# HV_Sense.net
KiCad netlist of a schematic drawn in Altium Designer
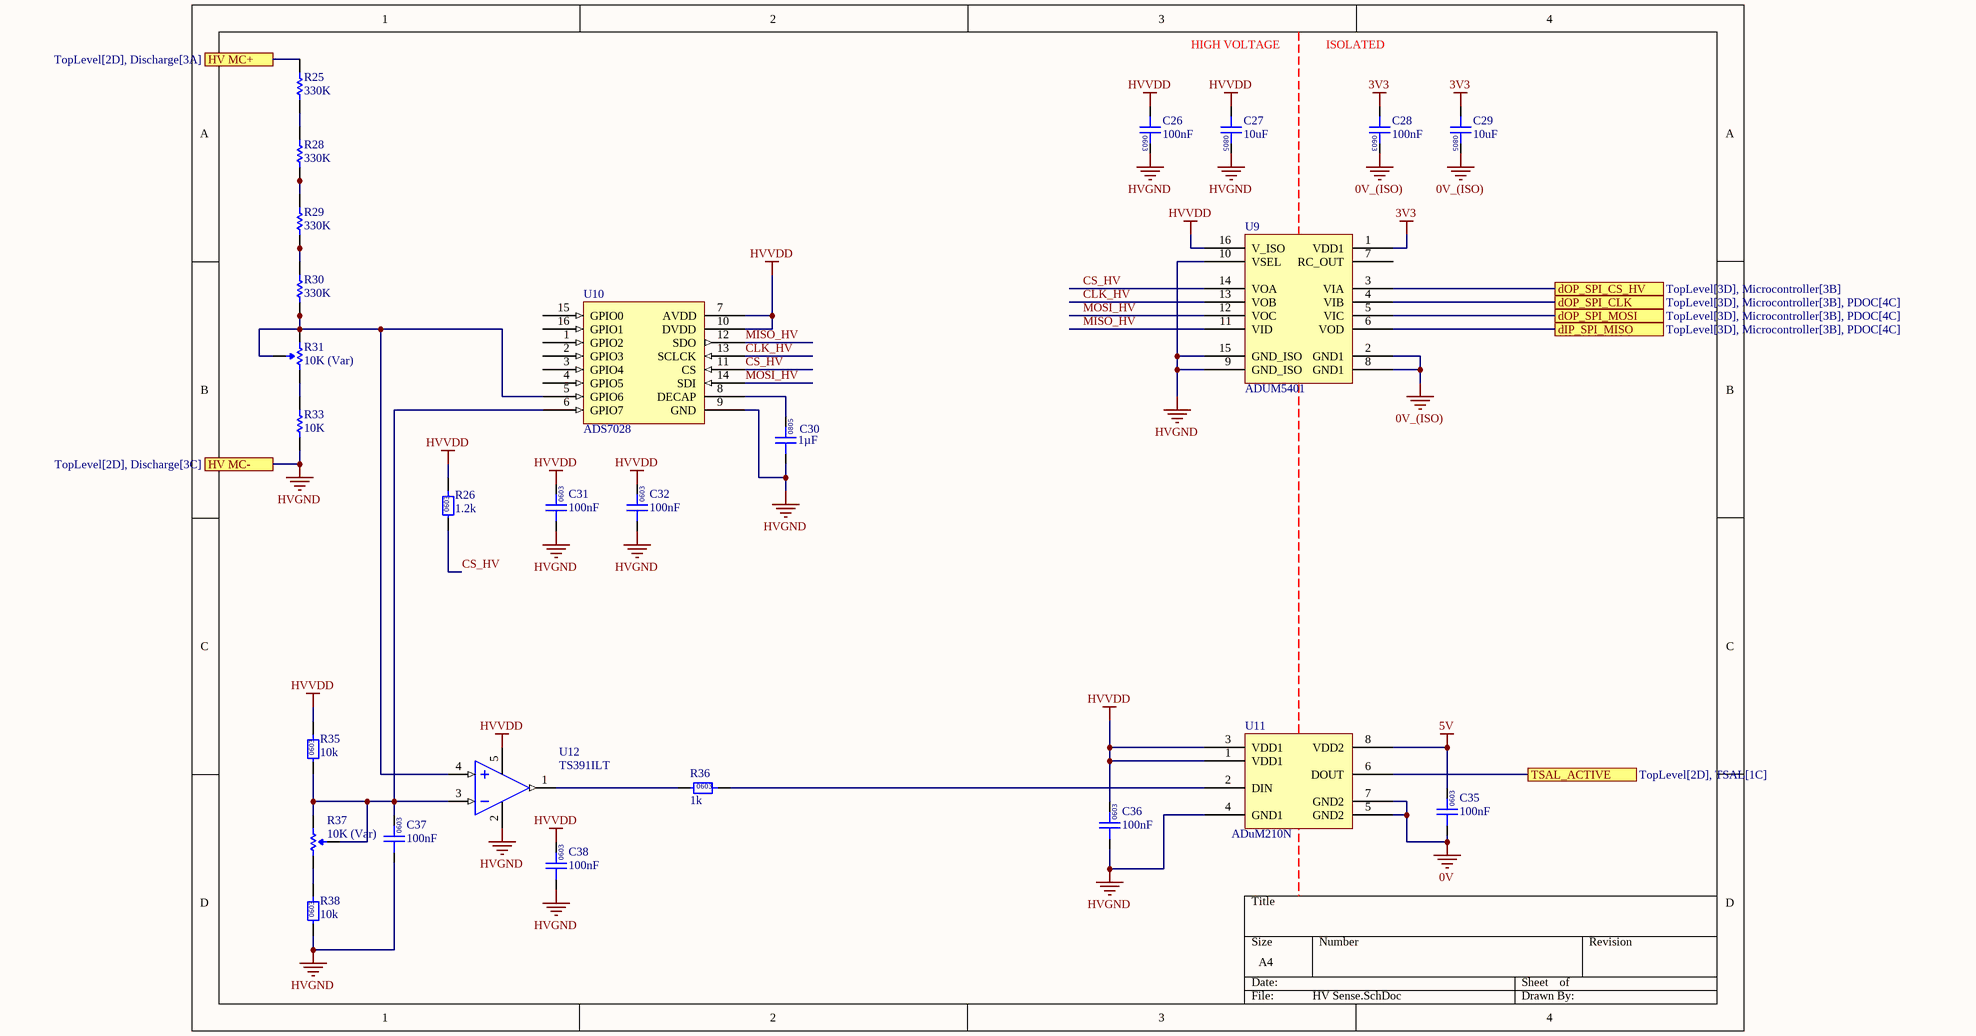
[diagram p0: HV Sense.SchDoc]

(export (version "E")
  (design (tool "Eeschema 10.0.6"))
  (components
    (comp (ref "C26")
      (value "100nF")
      (footprint "0603")
      (fields
        (field (name "PART NUMBER") "GCM188L81H104KA57D")
        (field (name "MANUFACTURER") "muRata")
        (field (name "TOLERANCE") "±10%")
      )
      (libsource (lib "ts_standard_library") (part "Capacitor 0603"))
    )
    (comp (ref "C27")
      (value "10uF")
      (footprint "0805")
      (fields
        (field (name "PART NUMBER") "GRM21BR6YA106KE43L")
        (field (name "MANUFACTURER") "muRata")
        (field (name "TOLERANCE") "10%")
      )
      (libsource (lib "ts_standard_library") (part "Capacitor 0805"))
    )
    (comp (ref "C28")
      (value "100nF")
      (footprint "0603")
      (fields
        (field (name "PART NUMBER") "GCM188L81H104KA57D")
        (field (name "MANUFACTURER") "muRata")
        (field (name "TOLERANCE") "±10%")
      )
      (libsource (lib "ts_standard_library") (part "Capacitor 0603"))
    )
    (comp (ref "C29")
      (value "10uF")
      (footprint "0805")
      (fields
        (field (name "PART NUMBER") "GRM21BR6YA106KE43L")
        (field (name "MANUFACTURER") "muRata")
        (field (name "TOLERANCE") "10%")
      )
      (libsource (lib "ts_standard_library") (part "Capacitor 0805"))
    )
    (comp (ref "C30")
      (value "1µF")
      (footprint "0805")
      (fields
        (field (name "PART NUMBER") "GCM21BR71H105KA03L")
        (field (name "MANUFACTURER") "muRata")
        (field (name "TOLERANCE") "±10%")
      )
      (libsource (lib "ts_standard_library") (part "Capacitor 0805"))
    )
    (comp (ref "C31")
      (value "100nF")
      (footprint "0603")
      (fields
        (field (name "PART NUMBER") "GCM188L81H104KA57D")
        (field (name "MANUFACTURER") "muRata")
        (field (name "TOLERANCE") "±10%")
      )
      (libsource (lib "ts_standard_library") (part "Capacitor 0603"))
    )
    (comp (ref "C32")
      (value "100nF")
      (footprint "0603")
      (fields
        (field (name "PART NUMBER") "GCM188L81H104KA57D")
        (field (name "MANUFACTURER") "muRata")
        (field (name "TOLERANCE") "±10%")
      )
      (libsource (lib "ts_standard_library") (part "Capacitor 0603"))
    )
    (comp (ref "C35")
      (value "100nF")
      (footprint "0603")
      (fields
        (field (name "PART NUMBER") "GCM188L81H104KA57D")
        (field (name "MANUFACTURER") "muRata")
        (field (name "TOLERANCE") "±10%")
      )
      (libsource (lib "ts_standard_library") (part "Capacitor 0603"))
    )
    (comp (ref "C36")
      (value "100nF")
      (footprint "0603")
      (fields
        (field (name "PART NUMBER") "GCM188L81H104KA57D")
        (field (name "MANUFACTURER") "muRata")
        (field (name "TOLERANCE") "±10%")
      )
      (libsource (lib "ts_standard_library") (part "Capacitor 0603"))
    )
    (comp (ref "C37")
      (value "100nF")
      (footprint "0603")
      (fields
        (field (name "PART NUMBER") "GCM188L81H104KA57D")
        (field (name "MANUFACTURER") "muRata")
        (field (name "TOLERANCE") "±10%")
      )
      (libsource (lib "ts_standard_library") (part "Capacitor 0603"))
    )
    (comp (ref "C38")
      (value "100nF")
      (footprint "0603")
      (fields
        (field (name "PART NUMBER") "GCM188L81H104KA57D")
        (field (name "MANUFACTURER") "muRata")
        (field (name "TOLERANCE") "±10%")
      )
      (libsource (lib "ts_standard_library") (part "Capacitor 0603"))
    )
    (comp (ref "R25")
      (value "330K")
      (footprint "VB 0207")
      (fields
        (field (name "PART NUMBER") "MMB02070C3303FB200")
        (field (name "MANUFACTURER") "Vishay Beyschlag")
        (field (name "TOLERANCE") "0.01")
      )
      (libsource (lib "ts_standard_library") (part "Resistor"))
    )
    (comp (ref "R26")
      (value "1.2k")
      (footprint "0603")
      (fields
        (field (name "PART NUMBER") "RC0603JR-071K2L")
        (field (name "MANUFACTURER") "YAGEO")
        (field (name "TOLERANCE") "0.01")
      )
      (libsource (lib "ts_standard_library") (part "Resistor 0603"))
    )
    (comp (ref "R28")
      (value "330K")
      (footprint "VB 0207")
      (fields
        (field (name "PART NUMBER") "MMB02070C3303FB200")
        (field (name "MANUFACTURER") "Vishay Beyschlag")
        (field (name "TOLERANCE") "0.01")
      )
      (libsource (lib "ts_standard_library") (part "Resistor"))
    )
    (comp (ref "R29")
      (value "330K")
      (footprint "VB 0207")
      (fields
        (field (name "PART NUMBER") "MMB02070C3303FB200")
        (field (name "MANUFACTURER") "Vishay Beyschlag")
        (field (name "TOLERANCE") "0.01")
      )
      (libsource (lib "ts_standard_library") (part "Resistor"))
    )
    (comp (ref "R30")
      (value "330K")
      (footprint "VB 0207")
      (fields
        (field (name "PART NUMBER") "MMB02070C3303FB200")
        (field (name "MANUFACTURER") "Vishay Beyschlag")
        (field (name "TOLERANCE") "0.01")
      )
      (libsource (lib "ts_standard_library") (part "Resistor"))
    )
    (comp (ref "R31")
      (value "10K (Var)")
      (footprint "B 3296")
      (fields
        (field (name "PART NUMBER") "3296W-1-103LF")
        (field (name "MANUFACTURER") "Bournes Inc")
        (field (name "TOLERANCE") "0.1")
      )
      (libsource (lib "ts_standard_library") (part "Resistor (Potentiometer)"))
    )
    (comp (ref "R33")
      (value "10K")
      (footprint "VB 0207")
      (fields
        (field (name "PART NUMBER") "MMB02070C1003FB200")
        (field (name "MANUFACTURER") "Vishay Beyschlag")
        (field (name "TOLERANCE") "0.01")
      )
      (libsource (lib "ts_standard_library") (part "Resistor"))
    )
    (comp (ref "R35")
      (value "10k")
      (footprint "0603")
      (fields
        (field (name "PART NUMBER") "RC0603FR-0710KL")
        (field (name "MANUFACTURER") "YAGEO")
        (field (name "TOLERANCE") "0.01")
      )
      (libsource (lib "ts_standard_library") (part "Resistor 0603"))
    )
    (comp (ref "R36")
      (value "1k")
      (footprint "0603")
      (fields
        (field (name "PART NUMBER") "RC0603FR-071KL")
        (field (name "MANUFACTURER") "YAGEO")
        (field (name "TOLERANCE") "0.01")
      )
      (libsource (lib "ts_standard_library") (part "Resistor 0603"))
    )
    (comp (ref "R37")
      (value "10K (Var)")
      (footprint "B 3296")
      (fields
        (field (name "PART NUMBER") "3296W-1-103LF")
        (field (name "MANUFACTURER") "Bournes Inc")
        (field (name "TOLERANCE") "0.1")
      )
      (libsource (lib "ts_standard_library") (part "Resistor (Potentiometer)"))
    )
    (comp (ref "R38")
      (value "10k")
      (footprint "0603")
      (fields
        (field (name "PART NUMBER") "RC0603FR-0710KL")
        (field (name "MANUFACTURER") "YAGEO")
        (field (name "TOLERANCE") "0.01")
      )
      (libsource (lib "ts_standard_library") (part "Resistor 0603"))
    )
    (comp (ref "U9")
      (value "ADUM5401")
      (footprint "AD 16-SOIC")
      (description "Quad Channel 2.5kV Digital Isolator with isoPower")
      (fields (field (name "MANUFACTURER") "Analogue Devices"))
      (libsource (lib "ts_standard_library") (part "ADUM5401"))
    )
    (comp (ref "U10")
      (value "ADS7028")
      (footprint "WFQN-16")
      (description "IC ADC 12BIT SAR 16WQFN")
      (fields (field (name "PART NUMBER") "ADS7028IRTER") (field (name "MANUFACTURER") "Texas Instruments"))
      (libsource (lib "ts_standard_library") (part "ADS7028IRTER"))
    )
    (comp (ref "U11")
      (value "ADuM210N")
      (footprint "SOIC-8W")
      (description "DIGITAL ISOLATOR, SINGLE CHANNEL")
      (libsource (lib "Team Swinburne") (part "ADuM210N"))
    )
    (comp (ref "U12")
      (value "TS391ILT")
      (footprint "ON SOT-23-5")
      (description "IC COMP LO PWR SGL V SOT 23-5L")
      (libsource (lib "Team Swinburne") (part "TS391ILT"))
    )
  )
  (nets
    (net (code "1") (name "/CLK_HV") (class "Default")
      (node (ref "U10") (pin "13") (pinfunction "SCLCK_13") (pintype "input"))
      (node (ref "U9") (pin "13") (pinfunction "VOB_13") (pintype "passive"))
    )
    (net (code "2") (name "/CS_HV") (class "Default")
      (node (ref "R26") (pin "1") (pinfunction "1_1") (pintype "passive"))
      (node (ref "U10") (pin "11") (pinfunction "CS_11") (pintype "input"))
      (node (ref "U9") (pin "14") (pinfunction "VOA_14") (pintype "passive"))
    )
    (net (code "3") (name "/HV MC+") (class "Default")
      (node (ref "R25") (pin "2") (pinfunction "2_2") (pintype "passive"))
    )
    (net (code "4") (name "/MISO_HV") (class "Default")
      (node (ref "U10") (pin "12") (pinfunction "SDO_12") (pintype "output"))
      (node (ref "U9") (pin "11") (pinfunction "VID_11") (pintype "passive"))
    )
    (net (code "5") (name "/MOSI_HV") (class "Default")
      (node (ref "U10") (pin "14") (pinfunction "SDI_14") (pintype "input"))
      (node (ref "U9") (pin "12") (pinfunction "VOC_12") (pintype "passive"))
    )
    (net (code "6") (name "/TSAL_ACTIVE") (class "Default")
      (node (ref "U11") (pin "6") (pinfunction "DOUT_6") (pintype "passive"))
    )
    (net (code "7") (name "/dIP_SPI_MISO") (class "Default")
      (node (ref "U9") (pin "6") (pinfunction "VOD_6") (pintype "passive"))
    )
    (net (code "8") (name "/dOP_SPI_CLK") (class "Default")
      (node (ref "U9") (pin "4") (pinfunction "VIB_4") (pintype "passive"))
    )
    (net (code "9") (name "/dOP_SPI_CS_HV") (class "Default")
      (node (ref "U9") (pin "3") (pinfunction "VIA_3") (pintype "passive"))
    )
    (net (code "10") (name "/dOP_SPI_MOSI") (class "Default")
      (node (ref "U9") (pin "5") (pinfunction "VIC_5") (pintype "passive"))
    )
    (net (code "11") (name "0V") (class "Default")
      (node (ref "C35") (pin "1") (pinfunction "1_1") (pintype "passive"))
      (node (ref "U11") (pin "5") (pinfunction "GND2_5") (pintype "passive"))
      (node (ref "U11") (pin "7") (pinfunction "GND2_7") (pintype "passive"))
    )
    (net (code "12") (name "0V_(ISO)") (class "Default")
      (node (ref "C28") (pin "2") (pinfunction "2_2") (pintype "passive"))
      (node (ref "C29") (pin "2") (pinfunction "2_2") (pintype "passive"))
      (node (ref "U9") (pin "2") (pinfunction "GND1_2") (pintype "passive"))
      (node (ref "U9") (pin "8") (pinfunction "GND1_8") (pintype "passive"))
    )
    (net (code "13") (name "3V3") (class "Default")
      (node (ref "C28") (pin "1") (pinfunction "1_1") (pintype "passive"))
      (node (ref "C29") (pin "1") (pinfunction "1_1") (pintype "passive"))
      (node (ref "U9") (pin "1") (pinfunction "VDD1_1") (pintype "passive"))
    )
    (net (code "14") (name "5V") (class "Default")
      (node (ref "C35") (pin "2") (pinfunction "2_2") (pintype "passive"))
      (node (ref "U11") (pin "8") (pinfunction "VDD2_8") (pintype "passive"))
    )
    (net (code "15") (name "HVGND") (class "Default")
      (node (ref "C26") (pin "2") (pinfunction "2_2") (pintype "passive"))
      (node (ref "C27") (pin "2") (pinfunction "2_2") (pintype "passive"))
      (node (ref "C30") (pin "1") (pinfunction "1_1") (pintype "passive"))
      (node (ref "C31") (pin "1") (pinfunction "1_1") (pintype "passive"))
      (node (ref "C32") (pin "1") (pinfunction "1_1") (pintype "passive"))
      (node (ref "C36") (pin "1") (pinfunction "1_1") (pintype "passive"))
      (node (ref "C37") (pin "1") (pinfunction "1_1") (pintype "passive"))
      (node (ref "C38") (pin "1") (pinfunction "1_1") (pintype "passive"))
      (node (ref "R33") (pin "1") (pinfunction "1_1") (pintype "passive"))
      (node (ref "R38") (pin "1") (pinfunction "1_1") (pintype "passive"))
      (node (ref "U10") (pin "9") (pinfunction "GND_9") (pintype "power_in"))
      (node (ref "U11") (pin "4") (pinfunction "GND1_4") (pintype "passive"))
      (node (ref "U12") (pin "2") (pinfunction "VCC-_2") (pintype "power_in"))
      (node (ref "U9") (pin "10") (pinfunction "VSEL_10") (pintype "passive"))
      (node (ref "U9") (pin "15") (pinfunction "GND_ISO_15") (pintype "passive"))
      (node (ref "U9") (pin "9") (pinfunction "GND_ISO_9") (pintype "passive"))
    )
    (net (code "16") (name "HVVDD") (class "Default")
      (node (ref "C26") (pin "1") (pinfunction "1_1") (pintype "passive"))
      (node (ref "C27") (pin "1") (pinfunction "1_1") (pintype "passive"))
      (node (ref "C31") (pin "2") (pinfunction "2_2") (pintype "passive"))
      (node (ref "C32") (pin "2") (pinfunction "2_2") (pintype "passive"))
      (node (ref "C36") (pin "2") (pinfunction "2_2") (pintype "passive"))
      (node (ref "C38") (pin "2") (pinfunction "2_2") (pintype "passive"))
      (node (ref "R26") (pin "2") (pinfunction "2_2") (pintype "passive"))
      (node (ref "R35") (pin "2") (pinfunction "2_2") (pintype "passive"))
      (node (ref "U10") (pin "10") (pinfunction "DVDD_10") (pintype "power_in"))
      (node (ref "U10") (pin "7") (pinfunction "AVDD_7") (pintype "power_in"))
      (node (ref "U11") (pin "1") (pinfunction "VDD1_1") (pintype "passive"))
      (node (ref "U11") (pin "3") (pinfunction "VDD1_3") (pintype "passive"))
      (node (ref "U12") (pin "5") (pinfunction "VCC+_5") (pintype "power_in"))
      (node (ref "U9") (pin "16") (pinfunction "V_ISO_16") (pintype "passive"))
    )
    (net (code "17") (name "Net-(R25-Pad1)") (class "Default")
      (node (ref "R25") (pin "1") (pinfunction "1_1") (pintype "passive"))
      (node (ref "R28") (pin "2") (pinfunction "2_2") (pintype "passive"))
    )
    (net (code "18") (name "Net-(R28-Pad1)") (class "Default")
      (node (ref "R28") (pin "1") (pinfunction "1_1") (pintype "passive"))
      (node (ref "R29") (pin "2") (pinfunction "2_2") (pintype "passive"))
    )
    (net (code "19") (name "Net-(R29-Pad1)") (class "Default")
      (node (ref "R29") (pin "1") (pinfunction "1_1") (pintype "passive"))
      (node (ref "R30") (pin "2") (pinfunction "2_2") (pintype "passive"))
    )
    (net (code "20") (name "Net-(R31-CCW)") (class "Default")
      (node (ref "R31") (pin "1") (pinfunction "CCW_1") (pintype "passive"))
      (node (ref "R33") (pin "2") (pinfunction "2_2") (pintype "passive"))
    )
    (net (code "21") (name "Net-(R31-CW)") (class "Default")
      (node (ref "R30") (pin "1") (pinfunction "1_1") (pintype "passive"))
      (node (ref "R31") (pin "2") (pinfunction "Wiper_2") (pintype "passive"))
      (node (ref "R31") (pin "3") (pinfunction "CW_3") (pintype "passive"))
      (node (ref "U10") (pin "5") (pinfunction "GPIO6_5") (pintype "input"))
      (node (ref "U12") (pin "4") (pinfunction "IIN+_4") (pintype "input"))
    )
    (net (code "22") (name "Net-(R37-CCW)") (class "Default")
      (node (ref "C37") (pin "2") (pinfunction "2_2") (pintype "passive"))
      (node (ref "R35") (pin "1") (pinfunction "1_1") (pintype "passive"))
      (node (ref "R37") (pin "1") (pinfunction "CCW_1") (pintype "passive"))
      (node (ref "R37") (pin "2") (pinfunction "Wiper_2") (pintype "passive"))
      (node (ref "U10") (pin "6") (pinfunction "GPIO7_6") (pintype "input"))
      (node (ref "U12") (pin "3") (pinfunction "IN-_3") (pintype "input"))
    )
    (net (code "23") (name "Net-(R37-CW)") (class "Default")
      (node (ref "R37") (pin "3") (pinfunction "CW_3") (pintype "passive"))
      (node (ref "R38") (pin "2") (pinfunction "2_2") (pintype "passive"))
    )
    (net (code "24") (name "Net-(U10-DECAP)") (class "Default")
      (node (ref "C30") (pin "2") (pinfunction "2_2") (pintype "passive"))
      (node (ref "U10") (pin "8") (pinfunction "DECAP_8") (pintype "power_in"))
    )
    (net (code "25") (name "Net-(U11-DIN)") (class "Default")
      (node (ref "R36") (pin "2") (pinfunction "2_2") (pintype "passive"))
      (node (ref "U11") (pin "2") (pinfunction "DIN_2") (pintype "passive"))
    )
    (net (code "26") (name "Net-(U12-OUT)") (class "Default")
      (node (ref "R36") (pin "1") (pinfunction "1_1") (pintype "passive"))
      (node (ref "U12") (pin "1") (pinfunction "OUT_1") (pintype "output"))
    )
    (net (code "27") (name "unconnected-(U9-RC_OUT-Pad7)") (class "Default")
      (node (ref "U9") (pin "7") (pinfunction "RC_OUT_7") (pintype "passive"))
    )
    (net (code "28") (name "unconnected-(U10-GPIO0-Pad15)") (class "Default")
      (node (ref "U10") (pin "15") (pinfunction "GPIO0_15") (pintype "input"))
    )
    (net (code "29") (name "unconnected-(U10-GPIO1-Pad16)") (class "Default")
      (node (ref "U10") (pin "16") (pinfunction "GPIO1_16") (pintype "input"))
    )
    (net (code "30") (name "unconnected-(U10-GPIO2-Pad1)") (class "Default")
      (node (ref "U10") (pin "1") (pinfunction "GPIO2_1") (pintype "input"))
    )
    (net (code "31") (name "unconnected-(U10-GPIO3-Pad2)") (class "Default")
      (node (ref "U10") (pin "2") (pinfunction "GPIO3_2") (pintype "input"))
    )
    (net (code "32") (name "unconnected-(U10-GPIO4-Pad3)") (class "Default")
      (node (ref "U10") (pin "3") (pinfunction "GPIO4_3") (pintype "input"))
    )
    (net (code "33") (name "unconnected-(U10-GPIO5-Pad4)") (class "Default")
      (node (ref "U10") (pin "4") (pinfunction "GPIO5_4") (pintype "input"))
    )
  )
)
